# Mez.net
KiCad netlist of a schematic drawn in Altium Designer
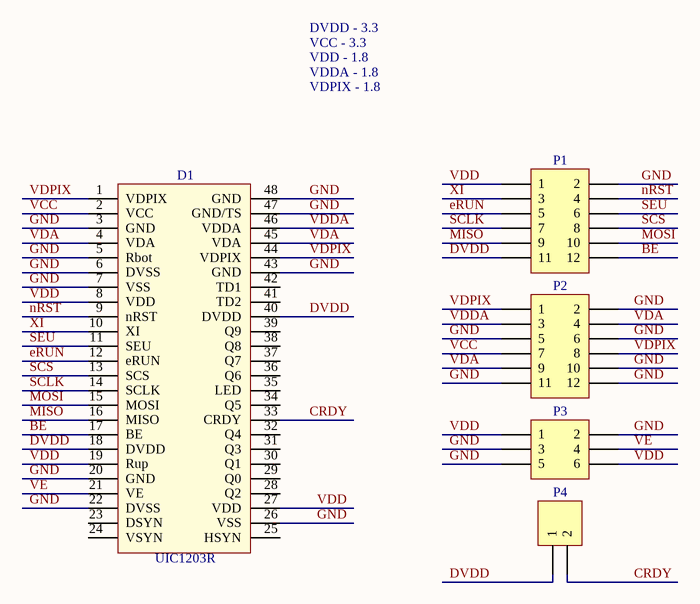
[diagram p0: Mez.SchDoc]

(export (version "E")
  (design (tool "Eeschema 10.0.6"))
  (components
    (comp (ref "D1") (value "UIC1203R") (footprint "UIC1203R") (libsource (lib "Schlib") (part "UIC1203R")))
    (comp (ref "P1")
      (value "Header 6X2")
      (footprint "HDR2X6")
      (description "Header, 6-Pin, Dual row")
      (fields (field (name "PUBLISHER") "Altium Limited"))
      (libsource (lib "Miscellaneous Connectors") (part "Header 6X2"))
    )
    (comp (ref "P2")
      (value "Header 6X2")
      (footprint "HDR2X6")
      (description "Header, 6-Pin, Dual row")
      (fields (field (name "PUBLISHER") "Altium Limited"))
      (libsource (lib "Miscellaneous Connectors") (part "Header 6X2"))
    )
    (comp (ref "P3")
      (value "Header 3X2")
      (footprint "HDR2X3")
      (description "Header, 3-Pin, Dual row")
      (fields (field (name "PUBLISHER") "Altium Limited"))
      (libsource (lib "Miscellaneous Connectors") (part "Header 3X2"))
    )
    (comp (ref "P4")
      (value "Header 2")
      (footprint "HDR1X2")
      (description "Header, 2-Pin")
      (fields (field (name "PUBLISHER") "Altium Limited"))
      (libsource (lib "Miscellaneous Connectors") (part "Header 2"))
    )
  )
  (nets
    (net (code "1") (name "/BE") (class "Default")
      (node (ref "D1") (pin "17") (pinfunction "BE_17") (pintype "passive"))
      (node (ref "P1") (pin "12") (pinfunction "12_12") (pintype "passive"))
    )
    (net (code "2") (name "/CRDY") (class "Default")
      (node (ref "D1") (pin "33") (pinfunction "CRDY_33") (pintype "passive"))
      (node (ref "P4") (pin "2") (pinfunction "2_2") (pintype "passive"))
    )
    (net (code "3") (name "/DVDD") (class "Default")
      (node (ref "D1") (pin "18") (pinfunction "DVDD_18") (pintype "passive"))
      (node (ref "D1") (pin "40") (pinfunction "DVDD_40") (pintype "passive"))
      (node (ref "P1") (pin "11") (pinfunction "11_11") (pintype "passive"))
      (node (ref "P4") (pin "1") (pinfunction "1_1") (pintype "passive"))
    )
    (net (code "4") (name "/GND") (class "Default")
      (node (ref "D1") (pin "20") (pinfunction "GND_20") (pintype "passive"))
      (node (ref "D1") (pin "22") (pinfunction "DVSS_22") (pintype "passive"))
      (node (ref "D1") (pin "26") (pinfunction "VSS_26") (pintype "passive"))
      (node (ref "D1") (pin "3") (pinfunction "GND_3") (pintype "passive"))
      (node (ref "D1") (pin "43") (pinfunction "GND_43") (pintype "passive"))
      (node (ref "D1") (pin "47") (pinfunction "GND/TS_47") (pintype "passive"))
      (node (ref "D1") (pin "48") (pinfunction "GND_48") (pintype "passive"))
      (node (ref "D1") (pin "5") (pinfunction "Rbot_5") (pintype "passive"))
      (node (ref "D1") (pin "6") (pinfunction "DVSS_6") (pintype "passive"))
      (node (ref "D1") (pin "7") (pinfunction "VSS_7") (pintype "passive"))
      (node (ref "P1") (pin "2") (pinfunction "2_2") (pintype "passive"))
      (node (ref "P2") (pin "10") (pinfunction "10_10") (pintype "passive"))
      (node (ref "P2") (pin "11") (pinfunction "11_11") (pintype "passive"))
      (node (ref "P2") (pin "12") (pinfunction "12_12") (pintype "passive"))
      (node (ref "P2") (pin "2") (pinfunction "2_2") (pintype "passive"))
      (node (ref "P2") (pin "5") (pinfunction "5_5") (pintype "passive"))
      (node (ref "P2") (pin "6") (pinfunction "6_6") (pintype "passive"))
      (node (ref "P3") (pin "2") (pinfunction "2_2") (pintype "passive"))
      (node (ref "P3") (pin "3") (pinfunction "3_3") (pintype "passive"))
      (node (ref "P3") (pin "5") (pinfunction "5_5") (pintype "passive"))
    )
    (net (code "5") (name "/MISO") (class "Default")
      (node (ref "D1") (pin "16") (pinfunction "MISO_16") (pintype "passive"))
      (node (ref "P1") (pin "9") (pinfunction "9_9") (pintype "passive"))
    )
    (net (code "6") (name "/MOSI") (class "Default")
      (node (ref "D1") (pin "15") (pinfunction "MOSI_15") (pintype "passive"))
      (node (ref "P1") (pin "10") (pinfunction "10_10") (pintype "passive"))
    )
    (net (code "7") (name "/SCLK") (class "Default")
      (node (ref "D1") (pin "14") (pinfunction "SCLK_14") (pintype "passive"))
      (node (ref "P1") (pin "7") (pinfunction "7_7") (pintype "passive"))
    )
    (net (code "8") (name "/SCS") (class "Default")
      (node (ref "D1") (pin "13") (pinfunction "SCS_13") (pintype "passive"))
      (node (ref "P1") (pin "8") (pinfunction "8_8") (pintype "passive"))
    )
    (net (code "9") (name "/SEU") (class "Default")
      (node (ref "D1") (pin "11") (pinfunction "SEU_11") (pintype "passive"))
      (node (ref "P1") (pin "6") (pinfunction "6_6") (pintype "passive"))
    )
    (net (code "10") (name "/VCC") (class "Default")
      (node (ref "D1") (pin "2") (pinfunction "VCC_2") (pintype "passive"))
      (node (ref "P2") (pin "7") (pinfunction "7_7") (pintype "passive"))
    )
    (net (code "11") (name "/VDA") (class "Default")
      (node (ref "D1") (pin "4") (pinfunction "VDA_4") (pintype "passive"))
      (node (ref "D1") (pin "45") (pinfunction "VDA_45") (pintype "passive"))
      (node (ref "P2") (pin "4") (pinfunction "4_4") (pintype "passive"))
      (node (ref "P2") (pin "9") (pinfunction "9_9") (pintype "passive"))
    )
    (net (code "12") (name "/VDD") (class "Default")
      (node (ref "D1") (pin "19") (pinfunction "Rup_19") (pintype "passive"))
      (node (ref "D1") (pin "27") (pinfunction "VDD_27") (pintype "passive"))
      (node (ref "D1") (pin "8") (pinfunction "VDD_8") (pintype "passive"))
      (node (ref "P1") (pin "1") (pinfunction "1_1") (pintype "passive"))
      (node (ref "P3") (pin "1") (pinfunction "1_1") (pintype "passive"))
      (node (ref "P3") (pin "6") (pinfunction "6_6") (pintype "passive"))
    )
    (net (code "13") (name "/VDDA") (class "Default")
      (node (ref "D1") (pin "46") (pinfunction "VDDA_46") (pintype "passive"))
      (node (ref "P2") (pin "3") (pinfunction "3_3") (pintype "passive"))
    )
    (net (code "14") (name "/VDPIX") (class "Default")
      (node (ref "D1") (pin "1") (pinfunction "VDPIX_1") (pintype "passive"))
      (node (ref "D1") (pin "44") (pinfunction "VDPIX_44") (pintype "passive"))
      (node (ref "P2") (pin "1") (pinfunction "1_1") (pintype "passive"))
      (node (ref "P2") (pin "8") (pinfunction "8_8") (pintype "passive"))
    )
    (net (code "15") (name "/VE") (class "Default")
      (node (ref "D1") (pin "21") (pinfunction "VE_21") (pintype "passive"))
      (node (ref "P3") (pin "4") (pinfunction "4_4") (pintype "passive"))
    )
    (net (code "16") (name "/XI") (class "Default")
      (node (ref "D1") (pin "10") (pinfunction "XI_10") (pintype "passive"))
      (node (ref "P1") (pin "3") (pinfunction "3_3") (pintype "passive"))
    )
    (net (code "17") (name "/eRUN") (class "Default")
      (node (ref "D1") (pin "12") (pinfunction "eRUN_12") (pintype "passive"))
      (node (ref "P1") (pin "5") (pinfunction "5_5") (pintype "passive"))
    )
    (net (code "18") (name "/nRST") (class "Default")
      (node (ref "D1") (pin "9") (pinfunction "nRST_9") (pintype "passive"))
      (node (ref "P1") (pin "4") (pinfunction "4_4") (pintype "passive"))
    )
    (net (code "19") (name "unconnected-(D1-DSYN-Pad23)") (class "Default")
      (node (ref "D1") (pin "23") (pinfunction "DSYN_23") (pintype "passive"))
    )
    (net (code "20") (name "unconnected-(D1-HSYN-Pad25)") (class "Default")
      (node (ref "D1") (pin "25") (pinfunction "HSYN_25") (pintype "passive"))
    )
    (net (code "21") (name "unconnected-(D1-LED-Pad35)") (class "Default")
      (node (ref "D1") (pin "35") (pinfunction "LED_35") (pintype "passive"))
    )
    (net (code "22") (name "unconnected-(D1-Q0-Pad29)") (class "Default")
      (node (ref "D1") (pin "29") (pinfunction "Q0_29") (pintype "passive"))
    )
    (net (code "23") (name "unconnected-(D1-Q1-Pad30)") (class "Default")
      (node (ref "D1") (pin "30") (pinfunction "Q1_30") (pintype "passive"))
    )
    (net (code "24") (name "unconnected-(D1-Q2-Pad28)") (class "Default")
      (node (ref "D1") (pin "28") (pinfunction "Q2_28") (pintype "passive"))
    )
    (net (code "25") (name "unconnected-(D1-Q3-Pad31)") (class "Default")
      (node (ref "D1") (pin "31") (pinfunction "Q3_31") (pintype "passive"))
    )
    (net (code "26") (name "unconnected-(D1-Q4-Pad32)") (class "Default")
      (node (ref "D1") (pin "32") (pinfunction "Q4_32") (pintype "passive"))
    )
    (net (code "27") (name "unconnected-(D1-Q5-Pad34)") (class "Default")
      (node (ref "D1") (pin "34") (pinfunction "Q5_34") (pintype "passive"))
    )
    (net (code "28") (name "unconnected-(D1-Q6-Pad36)") (class "Default")
      (node (ref "D1") (pin "36") (pinfunction "Q6_36") (pintype "passive"))
    )
    (net (code "29") (name "unconnected-(D1-Q7-Pad37)") (class "Default")
      (node (ref "D1") (pin "37") (pinfunction "Q7_37") (pintype "passive"))
    )
    (net (code "30") (name "unconnected-(D1-Q8-Pad38)") (class "Default")
      (node (ref "D1") (pin "38") (pinfunction "Q8_38") (pintype "passive"))
    )
    (net (code "31") (name "unconnected-(D1-Q9-Pad39)") (class "Default")
      (node (ref "D1") (pin "39") (pinfunction "Q9_39") (pintype "passive"))
    )
    (net (code "32") (name "unconnected-(D1-TD1-Pad42)") (class "Default")
      (node (ref "D1") (pin "42") (pinfunction "TD1_42") (pintype "passive"))
    )
    (net (code "33") (name "unconnected-(D1-TD2-Pad41)") (class "Default")
      (node (ref "D1") (pin "41") (pinfunction "TD2_41") (pintype "passive"))
    )
    (net (code "34") (name "unconnected-(D1-VSYN-Pad24)") (class "Default")
      (node (ref "D1") (pin "24") (pinfunction "VSYN_24") (pintype "passive"))
    )
  )
)
